# receiver.net
KiCad netlist of a schematic drawn in EAGLE
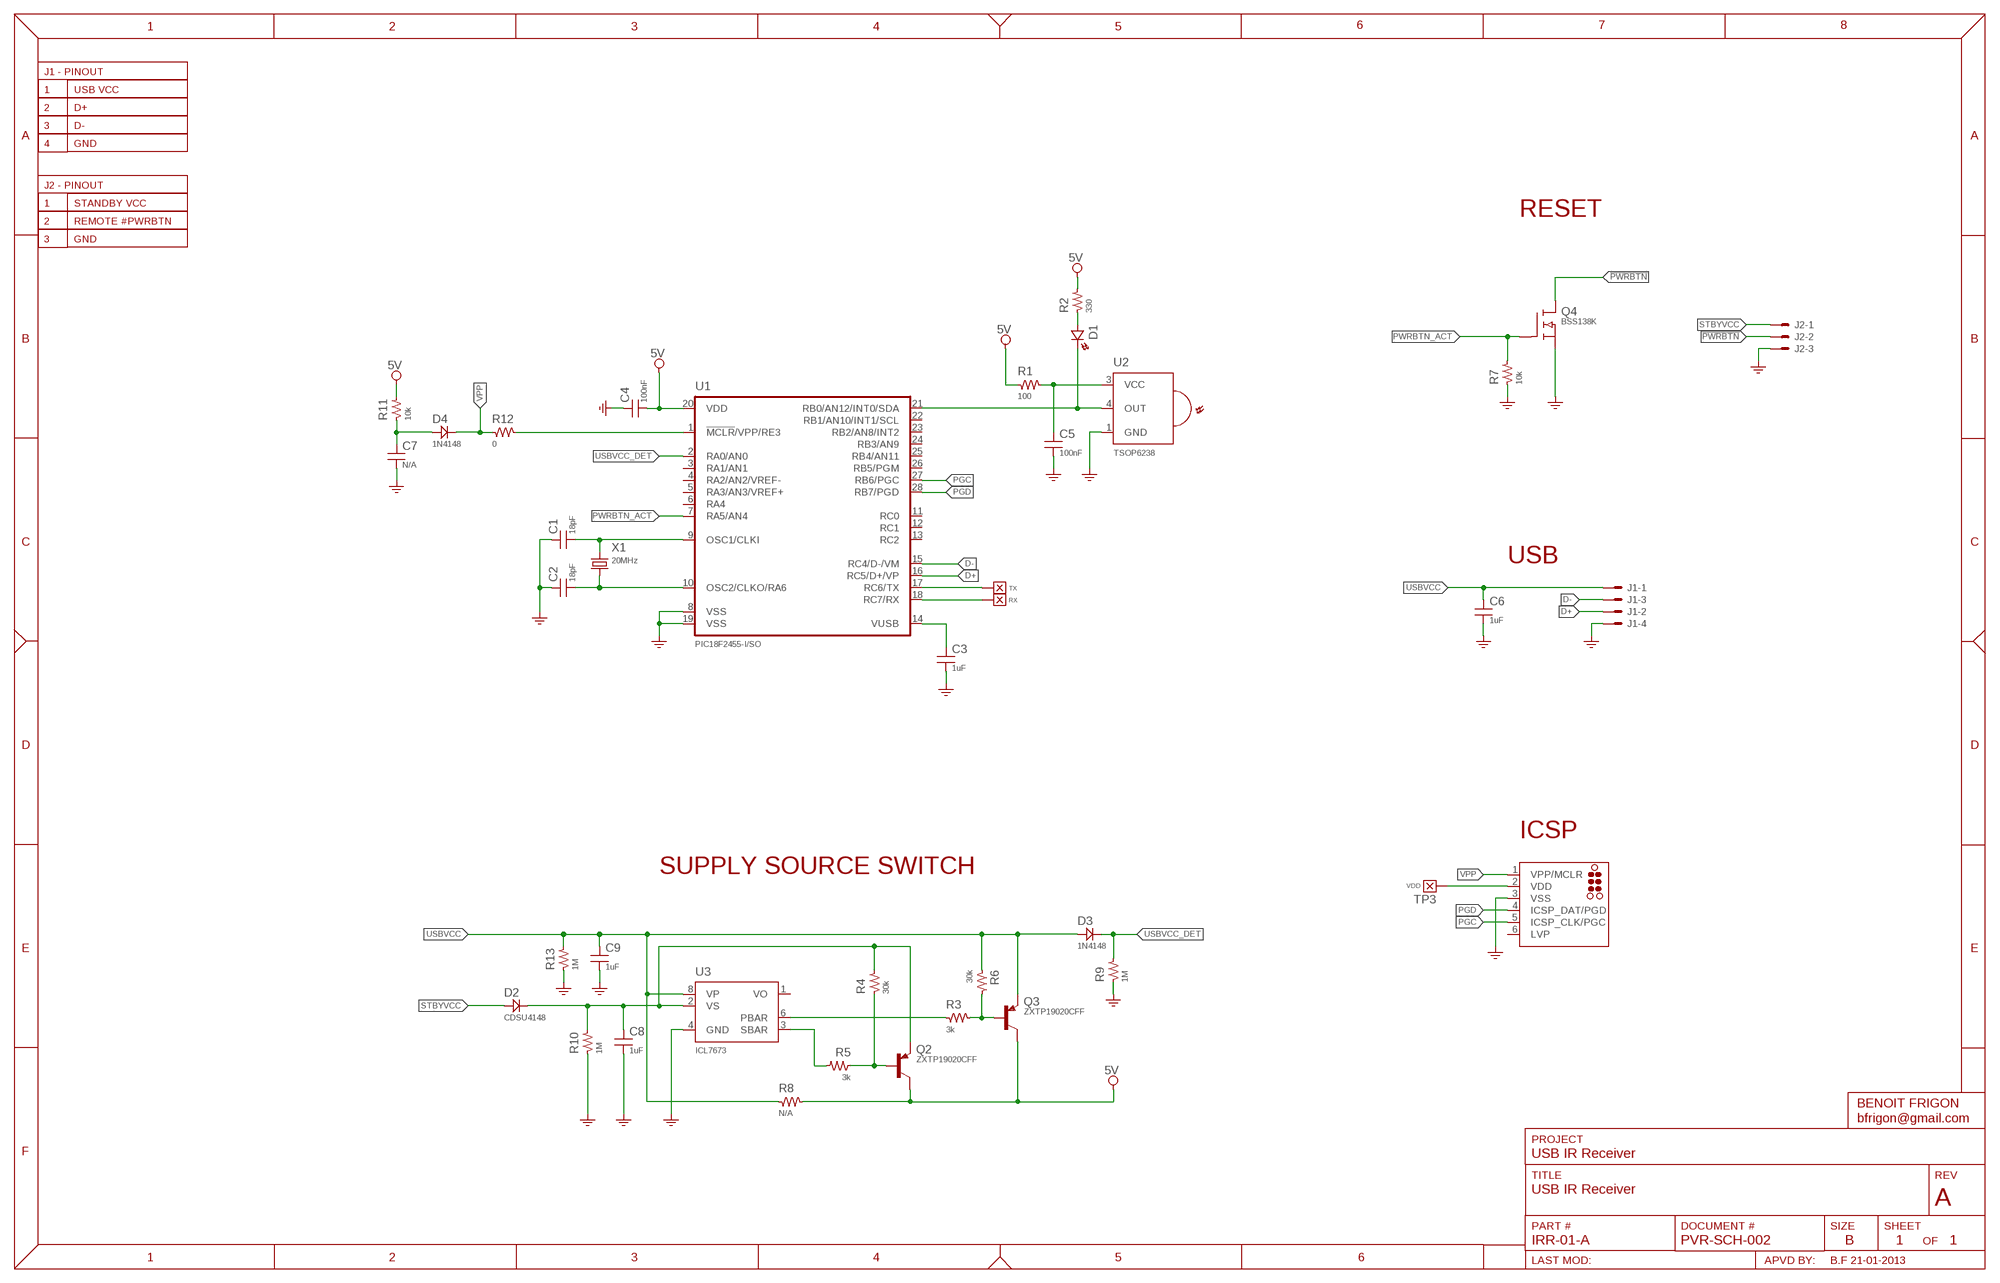
[diagram p0: schematic, sheet 1]

(export (version "E")
  (design (tool "Eeschema 10.0.6"))
  (components
    (comp (ref "C1")
      (value "18pF")
      (footprint "eagle-import:SMD_0603")
      (description "{DESCRIPTION} - SMT 0603 - {value}")
      (fields (field (name "PACKAGE") "SMT 0603"))
      (libsource (lib "eagle-import") (part "CAP-0603"))
    )
    (comp (ref "C2")
      (value "18pF")
      (footprint "eagle-import:SMD_0603")
      (description "{DESCRIPTION} - SMT 0603 - {value}")
      (fields (field (name "PACKAGE") "SMT 0603"))
      (libsource (lib "eagle-import") (part "CAP-0603"))
    )
    (comp (ref "C3")
      (value "1uF")
      (footprint "eagle-import:SMD_0603")
      (description "{DESCRIPTION} - SMT 0603 - {value}")
      (fields (field (name "PACKAGE") "SMT 0603"))
      (libsource (lib "eagle-import") (part "CAP-0603"))
    )
    (comp (ref "C4")
      (value "100nF")
      (footprint "eagle-import:SMD_0603")
      (libsource (lib "eagle-import") (part "CAP-0603"))
    )
    (comp (ref "C5")
      (value "100nF")
      (footprint "eagle-import:SMD_0603")
      (libsource (lib "eagle-import") (part "CAP-0603"))
    )
    (comp (ref "C6")
      (value "1uF")
      (footprint "eagle-import:SMD_0603")
      (description "{DESCRIPTION} - SMT 0603 - {value}")
      (fields (field (name "PACKAGE") "SMT 0603"))
      (libsource (lib "eagle-import") (part "CAP-0603"))
    )
    (comp (ref "C7")
      (value "N/A")
      (footprint "eagle-import:SMD_0603")
      (libsource (lib "eagle-import") (part "CAP-0603"))
    )
    (comp (ref "C8")
      (value "1uF")
      (footprint "eagle-import:SMD_0603")
      (libsource (lib "eagle-import") (part "CAP-0603"))
    )
    (comp (ref "C9")
      (value "1uF")
      (footprint "eagle-import:SMD_0603")
      (libsource (lib "eagle-import") (part "CAP-0603"))
    )
    (comp (ref "D1")
      (value "{ATTR:COLOR}")
      (footprint "eagle-import:CHIPLED_0805")
      (libsource (lib "eagle-import") (part "LED-0805"))
    )
    (comp (ref "D2")
      (value "CDSU4148")
      (footprint "eagle-import:DIODE_0603")
      (libsource (lib "eagle-import") (part "DIODE-0603"))
    )
    (comp (ref "D3")
      (value "1N4148")
      (footprint "eagle-import:DIODE_0603")
      (libsource (lib "eagle-import") (part "DIODE-0603"))
    )
    (comp (ref "D4")
      (value "1N4148")
      (footprint "eagle-import:DIODE_0603")
      (libsource (lib "eagle-import") (part "DIODE-0603"))
    )
    (comp (ref "J1")
      (value "SNG-100-HEADER-04-FL-RA")
      (footprint "eagle-import:22-05-3041")
      (fields (field (name "MFG") "Molex"))
      (libsource (lib "eagle-import") (part "SNG-100-HEADER-04-FL-RA"))
    )
    (comp (ref "J2")
      (value "SNG-100-HEADER-03-FL-RA")
      (footprint "eagle-import:22-05-3031")
      (fields (field (name "MFG") "Molex"))
      (libsource (lib "eagle-import") (part "SNG-100-HEADER-03-FL-RA"))
    )
    (comp (ref "J10")
      (value "TC2030-MCP")
      (footprint "eagle-import:TC2030-MCP")
      (fields (field (name "MFG") "Tag-Connect"))
      (libsource (lib "eagle-import") (part "TC2030-MCP"))
    )
    (comp (ref "Q2")
      (value "ZXTP19020CFF")
      (footprint "eagle-import:SOT23")
      (fields (field (name "MFG") "Zetex"))
      (libsource (lib "eagle-import") (part "ZXTP19020CFF"))
    )
    (comp (ref "Q3")
      (value "ZXTP19020CFF")
      (footprint "eagle-import:SOT23")
      (fields (field (name "MFG") "Zetex"))
      (libsource (lib "eagle-import") (part "ZXTP19020CFF"))
    )
    (comp (ref "Q4")
      (value "BSS138K")
      (footprint "eagle-import:SOT23")
      (libsource (lib "eagle-import") (part "BSS138K"))
    )
    (comp (ref "R1")
      (value "100")
      (footprint "eagle-import:SMD_0603")
      (description "{DESCRIPTION} - SMT 0603 - {VALUE}")
      (fields (field (name "PACKAGE") "SMT 0603"))
      (libsource (lib "eagle-import") (part "RES-0603"))
    )
    (comp (ref "R2")
      (value "330")
      (footprint "eagle-import:SMD_0603")
      (description "{DESCRIPTION} - SMT 0603 - {VALUE}")
      (fields (field (name "PACKAGE") "SMT 0603"))
      (libsource (lib "eagle-import") (part "RES-0603"))
    )
    (comp (ref "R3")
      (value "3k")
      (footprint "eagle-import:SMD_0603")
      (libsource (lib "eagle-import") (part "RES-0603"))
    )
    (comp (ref "R4")
      (value "30k")
      (footprint "eagle-import:SMD_0603")
      (libsource (lib "eagle-import") (part "RES-0603"))
    )
    (comp (ref "R5")
      (value "3k")
      (footprint "eagle-import:SMD_0603")
      (libsource (lib "eagle-import") (part "RES-0603"))
    )
    (comp (ref "R6")
      (value "30k")
      (footprint "eagle-import:SMD_0603")
      (libsource (lib "eagle-import") (part "RES-0603"))
    )
    (comp (ref "R7")
      (value "10k")
      (footprint "eagle-import:SMD_0603")
      (libsource (lib "eagle-import") (part "RES-0603"))
    )
    (comp (ref "R8")
      (value "N/A")
      (footprint "eagle-import:SMD_0805")
      (description "{DESCRIPTION} - SMT 0805 - {VALUE}")
      (fields (field (name "PACKAGE") "SMT 0805"))
      (libsource (lib "eagle-import") (part "RES-0805"))
    )
    (comp (ref "R9")
      (value "1M")
      (footprint "eagle-import:SMD_0603")
      (libsource (lib "eagle-import") (part "RES-0603"))
    )
    (comp (ref "R10")
      (value "1M")
      (footprint "eagle-import:SMD_0603")
      (libsource (lib "eagle-import") (part "RES-0603"))
    )
    (comp (ref "R11")
      (value "10k")
      (footprint "eagle-import:SMD_0603")
      (libsource (lib "eagle-import") (part "RES-0603"))
    )
    (comp (ref "R12")
      (value "0")
      (footprint "eagle-import:SMD_0603")
      (libsource (lib "eagle-import") (part "RES-0603"))
    )
    (comp (ref "R13")
      (value "1M")
      (footprint "eagle-import:SMD_0603")
      (libsource (lib "eagle-import") (part "RES-0603"))
    )
    (comp (ref "TP1")
      (value "TX")
      (footprint "eagle-import:TP_050")
      (libsource (lib "eagle-import") (part "TEST_POINT-050"))
    )
    (comp (ref "TP2")
      (value "RX")
      (footprint "eagle-import:TP_050")
      (libsource (lib "eagle-import") (part "TEST_POINT-050"))
    )
    (comp (ref "TP3")
      (value "VDD")
      (footprint "eagle-import:TP_050")
      (libsource (lib "eagle-import") (part "TEST_POINT-050"))
    )
    (comp (ref "U1")
      (value "PIC18F2455-I/SO")
      (footprint "eagle-import:SOIC28")
      (fields (field (name "MFG") "Microchip"))
      (libsource (lib "eagle-import") (part "PIC18F2-?I/SO455"))
    )
    (comp (ref "U2")
      (value "TSOP6238")
      (footprint "eagle-import:TSOP62XX")
      (fields (field (name "MFG") "Vishay Semiconductors"))
      (libsource (lib "eagle-import") (part "TSOP6238"))
    )
    (comp (ref "U3")
      (value "ICL7673")
      (footprint "eagle-import:SOIC8")
      (fields (field (name "MFG") "Intersil"))
      (libsource (lib "eagle-import") (part "ICL7673"))
    )
    (comp (ref "X1")
      (value "20MHz")
      (footprint "eagle-import:SM49")
      (fields (field (name "MFG") "Cardinal Components"))
      (libsource (lib "eagle-import") (part "XTALSM49"))
    )
  )
  (nets
    (net (code "1") (name "/VO") (class "Default")
      (node (ref "U3") (pin "1") (pinfunction "VO_1") (pintype "power_in"))
    )
    (net (code "2") (name "/~{PWRBTN}") (class "Default")
      (node (ref "J2") (pin "2") (pinfunction "S_2") (pintype "bidirectional"))
      (node (ref "Q4") (pin "3") (pinfunction "D_3") (pintype "passive"))
    )
    (net (code "3") (name "5V") (class "Default")
      (node (ref "C4") (pin "2") (pinfunction "2_2") (pintype "passive"))
      (node (ref "Q2") (pin "3") (pinfunction "C_3") (pintype "passive"))
      (node (ref "Q3") (pin "3") (pinfunction "C_3") (pintype "passive"))
      (node (ref "R1") (pin "1") (pinfunction "1_1") (pintype "passive"))
      (node (ref "R11") (pin "2") (pinfunction "2_2") (pintype "passive"))
      (node (ref "R2") (pin "2") (pinfunction "2_2") (pintype "passive"))
      (node (ref "R8") (pin "2") (pinfunction "2_2") (pintype "passive"))
      (node (ref "U1") (pin "20") (pinfunction "VDD_20") (pintype "bidirectional"))
    )
    (net (code "4") (name "D+") (class "Default")
      (node (ref "J1") (pin "2") (pinfunction "S_2") (pintype "bidirectional"))
      (node (ref "U1") (pin "16") (pinfunction "RC5/D+/VP_16") (pintype "bidirectional"))
    )
    (net (code "5") (name "D-") (class "Default")
      (node (ref "J1") (pin "3") (pinfunction "S_3") (pintype "bidirectional"))
      (node (ref "U1") (pin "15") (pinfunction "RC4/D-/VM_15") (pintype "bidirectional"))
    )
    (net (code "6") (name "GND") (class "Default")
      (node (ref "C1") (pin "1") (pinfunction "1_1") (pintype "passive"))
      (node (ref "C2") (pin "1") (pinfunction "1_1") (pintype "passive"))
      (node (ref "C3") (pin "2") (pinfunction "2_2") (pintype "passive"))
      (node (ref "C4") (pin "1") (pinfunction "1_1") (pintype "passive"))
      (node (ref "C5") (pin "2") (pinfunction "2_2") (pintype "passive"))
      (node (ref "C6") (pin "2") (pinfunction "2_2") (pintype "passive"))
      (node (ref "C7") (pin "2") (pinfunction "2_2") (pintype "passive"))
      (node (ref "C8") (pin "2") (pinfunction "2_2") (pintype "passive"))
      (node (ref "C9") (pin "2") (pinfunction "2_2") (pintype "passive"))
      (node (ref "J1") (pin "4") (pinfunction "S_4") (pintype "bidirectional"))
      (node (ref "J10") (pin "3") (pinfunction "VSS_3") (pintype "power_in"))
      (node (ref "J2") (pin "3") (pinfunction "S_3") (pintype "bidirectional"))
      (node (ref "Q4") (pin "2") (pinfunction "S_2") (pintype "passive"))
      (node (ref "R10") (pin "1") (pinfunction "1_1") (pintype "passive"))
      (node (ref "R13") (pin "1") (pinfunction "1_1") (pintype "passive"))
      (node (ref "R7") (pin "1") (pinfunction "1_1") (pintype "passive"))
      (node (ref "R9") (pin "1") (pinfunction "1_1") (pintype "passive"))
      (node (ref "U1") (pin "19") (pinfunction "VSS_19") (pintype "bidirectional"))
      (node (ref "U1") (pin "8") (pinfunction "VSS_8") (pintype "bidirectional"))
      (node (ref "U2") (pin "1") (pinfunction "GND_1") (pintype "bidirectional"))
      (node (ref "U3") (pin "4") (pinfunction "GND_4") (pintype "power_in"))
    )
    (net (code "7") (name "Net-(C7-Pad1)") (class "Default")
      (node (ref "C7") (pin "1") (pinfunction "1_1") (pintype "passive"))
      (node (ref "D4") (pin "A") (pinfunction "A_A") (pintype "passive"))
      (node (ref "R11") (pin "1") (pinfunction "1_1") (pintype "passive"))
    )
    (net (code "8") (name "Net-(D1-PadA)") (class "Default")
      (node (ref "D1") (pin "A") (pinfunction "A_A") (pintype "passive"))
      (node (ref "R2") (pin "1") (pinfunction "1_1") (pintype "passive"))
    )
    (net (code "9") (name "Net-(J10-VDD)") (class "Default")
      (node (ref "J10") (pin "2") (pinfunction "VDD_2") (pintype "power_in"))
      (node (ref "TP3") (pin "1") (pinfunction "P$1_1") (pintype "bidirectional"))
    )
    (net (code "10") (name "Net-(Q2-B)") (class "Default")
      (node (ref "Q2") (pin "1") (pinfunction "B_1") (pintype "passive"))
      (node (ref "R4") (pin "1") (pinfunction "1_1") (pintype "passive"))
      (node (ref "R5") (pin "1") (pinfunction "1_1") (pintype "passive"))
    )
    (net (code "11") (name "Net-(Q2-E)") (class "Default")
      (node (ref "C8") (pin "1") (pinfunction "1_1") (pintype "passive"))
      (node (ref "D2") (pin "K") (pinfunction "K_K") (pintype "passive"))
      (node (ref "Q2") (pin "2") (pinfunction "E_2") (pintype "passive"))
      (node (ref "R10") (pin "2") (pinfunction "2_2") (pintype "passive"))
      (node (ref "R4") (pin "2") (pinfunction "2_2") (pintype "passive"))
      (node (ref "U3") (pin "2") (pinfunction "VS_2") (pintype "power_in"))
    )
    (net (code "12") (name "Net-(Q3-B)") (class "Default")
      (node (ref "Q3") (pin "1") (pinfunction "B_1") (pintype "passive"))
      (node (ref "R3") (pin "2") (pinfunction "2_2") (pintype "passive"))
      (node (ref "R6") (pin "2") (pinfunction "2_2") (pintype "passive"))
    )
    (net (code "13") (name "Net-(TP1-P$1)") (class "Default")
      (node (ref "TP1") (pin "1") (pinfunction "P$1_1") (pintype "bidirectional"))
      (node (ref "U1") (pin "17") (pinfunction "RC6/TX_17") (pintype "bidirectional"))
    )
    (net (code "14") (name "Net-(TP2-P$1)") (class "Default")
      (node (ref "TP2") (pin "1") (pinfunction "P$1_1") (pintype "bidirectional"))
      (node (ref "U1") (pin "18") (pinfunction "RC7/RX_18") (pintype "bidirectional"))
    )
    (net (code "15") (name "Net-(U1-OSC1{slash}CLKI)") (class "Default")
      (node (ref "C1") (pin "2") (pinfunction "2_2") (pintype "passive"))
      (node (ref "U1") (pin "9") (pinfunction "OSC1/CLKI_9") (pintype "bidirectional"))
      (node (ref "X1") (pin "1") (pinfunction "1_1") (pintype "passive"))
    )
    (net (code "16") (name "Net-(U1-OSC2{slash}CLKO{slash}RA6)") (class "Default")
      (node (ref "C2") (pin "2") (pinfunction "2_2") (pintype "passive"))
      (node (ref "U1") (pin "10") (pinfunction "OSC2/CLKO/RA6_10") (pintype "bidirectional"))
      (node (ref "X1") (pin "2") (pinfunction "2_2") (pintype "passive"))
    )
    (net (code "17") (name "Net-(U1-RB0{slash}AN12{slash}INT0{slash}SDA)") (class "Default")
      (node (ref "D1") (pin "K") (pinfunction "K_K") (pintype "passive"))
      (node (ref "U1") (pin "21") (pinfunction "RB0/AN12/INT0/SDA_21") (pintype "bidirectional"))
      (node (ref "U2") (pin "4") (pinfunction "OUT_4") (pintype "output"))
    )
    (net (code "18") (name "Net-(U1-VUSB)") (class "Default")
      (node (ref "C3") (pin "1") (pinfunction "1_1") (pintype "passive"))
      (node (ref "U1") (pin "14") (pinfunction "VUSB_14") (pintype "bidirectional"))
    )
    (net (code "19") (name "Net-(U1-~{MCLR}{slash}VPP{slash}RE3)") (class "Default")
      (node (ref "R12") (pin "2") (pinfunction "2_2") (pintype "passive"))
      (node (ref "U1") (pin "1") (pinfunction "~{MCLR}/VPP/RE3_1") (pintype "bidirectional"))
    )
    (net (code "20") (name "Net-(U2-VCC)") (class "Default")
      (node (ref "C5") (pin "1") (pinfunction "1_1") (pintype "passive"))
      (node (ref "R1") (pin "2") (pinfunction "2_2") (pintype "passive"))
      (node (ref "U2") (pin "3") (pinfunction "VCC_3") (pintype "bidirectional"))
    )
    (net (code "21") (name "Net-(U3-PBAR)") (class "Default")
      (node (ref "R3") (pin "1") (pinfunction "1_1") (pintype "passive"))
      (node (ref "U3") (pin "6") (pinfunction "PBAR_6") (pintype "output"))
    )
    (net (code "22") (name "Net-(U3-SBAR)") (class "Default")
      (node (ref "R5") (pin "2") (pinfunction "2_2") (pintype "passive"))
      (node (ref "U3") (pin "3") (pinfunction "SBAR_3") (pintype "output"))
    )
    (net (code "23") (name "PGC") (class "Default")
      (node (ref "J10") (pin "5") (pinfunction "ICSP_CLK/PGC_5") (pintype "output"))
      (node (ref "U1") (pin "27") (pinfunction "RB6/PGC_27") (pintype "bidirectional"))
    )
    (net (code "24") (name "PGD") (class "Default")
      (node (ref "J10") (pin "4") (pinfunction "ICSP_DAT/PGD_4") (pintype "bidirectional"))
      (node (ref "U1") (pin "28") (pinfunction "RB7/PGD_28") (pintype "bidirectional"))
    )
    (net (code "25") (name "PWRBTN_ACT") (class "Default")
      (node (ref "Q4") (pin "1") (pinfunction "G_1") (pintype "passive"))
      (node (ref "R7") (pin "2") (pinfunction "2_2") (pintype "passive"))
      (node (ref "U1") (pin "7") (pinfunction "RA5/AN4_7") (pintype "bidirectional"))
    )
    (net (code "26") (name "STBYVCC") (class "Default")
      (node (ref "D2") (pin "A") (pinfunction "A_A") (pintype "passive"))
      (node (ref "J2") (pin "1") (pinfunction "S_1") (pintype "bidirectional"))
    )
    (net (code "27") (name "USBVCC") (class "Default")
      (node (ref "C6") (pin "1") (pinfunction "1_1") (pintype "passive"))
      (node (ref "C9") (pin "1") (pinfunction "1_1") (pintype "passive"))
      (node (ref "D3") (pin "A") (pinfunction "A_A") (pintype "passive"))
      (node (ref "J1") (pin "1") (pinfunction "S_1") (pintype "bidirectional"))
      (node (ref "Q3") (pin "2") (pinfunction "E_2") (pintype "passive"))
      (node (ref "R13") (pin "2") (pinfunction "2_2") (pintype "passive"))
      (node (ref "R6") (pin "1") (pinfunction "1_1") (pintype "passive"))
      (node (ref "R8") (pin "1") (pinfunction "1_1") (pintype "passive"))
      (node (ref "U3") (pin "8") (pinfunction "VP_8") (pintype "power_in"))
    )
    (net (code "28") (name "USBVCC_DET") (class "Default")
      (node (ref "D3") (pin "K") (pinfunction "K_K") (pintype "passive"))
      (node (ref "R9") (pin "2") (pinfunction "2_2") (pintype "passive"))
      (node (ref "U1") (pin "2") (pinfunction "RA0/AN0_2") (pintype "bidirectional"))
    )
    (net (code "29") (name "VPP") (class "Default")
      (node (ref "D4") (pin "K") (pinfunction "K_K") (pintype "passive"))
      (node (ref "J10") (pin "1") (pinfunction "VPP/MCLR_1") (pintype "passive"))
      (node (ref "R12") (pin "1") (pinfunction "1_1") (pintype "passive"))
    )
    (net (code "30") (name "unconnected-(J10-LVP-Pad6)") (class "Default")
      (node (ref "J10") (pin "6") (pinfunction "LVP_6") (pintype "bidirectional"))
    )
    (net (code "31") (name "unconnected-(U1-RA1{slash}AN1-Pad3)") (class "Default")
      (node (ref "U1") (pin "3") (pinfunction "RA1/AN1_3") (pintype "bidirectional"))
    )
    (net (code "32") (name "unconnected-(U1-RA2{slash}AN2{slash}VREF--Pad4)") (class "Default")
      (node (ref "U1") (pin "4") (pinfunction "RA2/AN2/VREF-_4") (pintype "bidirectional"))
    )
    (net (code "33") (name "unconnected-(U1-RA3{slash}AN3{slash}VREF+-Pad5)") (class "Default")
      (node (ref "U1") (pin "5") (pinfunction "RA3/AN3/VREF+_5") (pintype "bidirectional"))
    )
    (net (code "34") (name "unconnected-(U1-RA4-Pad6)") (class "Default")
      (node (ref "U1") (pin "6") (pinfunction "RA4_6") (pintype "bidirectional"))
    )
    (net (code "35") (name "unconnected-(U1-RB1{slash}AN10{slash}INT1{slash}SCL-Pad22)") (class "Default")
      (node (ref "U1") (pin "22") (pinfunction "RB1/AN10/INT1/SCL_22") (pintype "bidirectional"))
    )
    (net (code "36") (name "unconnected-(U1-RB2{slash}AN8{slash}INT2-Pad23)") (class "Default")
      (node (ref "U1") (pin "23") (pinfunction "RB2/AN8/INT2_23") (pintype "bidirectional"))
    )
    (net (code "37") (name "unconnected-(U1-RB3{slash}AN9-Pad24)") (class "Default")
      (node (ref "U1") (pin "24") (pinfunction "RB3/AN9_24") (pintype "bidirectional"))
    )
    (net (code "38") (name "unconnected-(U1-RB4{slash}AN11-Pad25)") (class "Default")
      (node (ref "U1") (pin "25") (pinfunction "RB4/AN11_25") (pintype "bidirectional"))
    )
    (net (code "39") (name "unconnected-(U1-RB5{slash}PGM-Pad26)") (class "Default")
      (node (ref "U1") (pin "26") (pinfunction "RB5/PGM_26") (pintype "bidirectional"))
    )
    (net (code "40") (name "unconnected-(U1-RC0-Pad11)") (class "Default")
      (node (ref "U1") (pin "11") (pinfunction "RC0_11") (pintype "bidirectional"))
    )
    (net (code "41") (name "unconnected-(U1-RC1-Pad12)") (class "Default")
      (node (ref "U1") (pin "12") (pinfunction "RC1_12") (pintype "bidirectional"))
    )
    (net (code "42") (name "unconnected-(U1-RC2-Pad13)") (class "Default")
      (node (ref "U1") (pin "13") (pinfunction "RC2_13") (pintype "bidirectional"))
    )
  )
)
